# micro.net
KiCad netlist of a schematic drawn in Altium Designer
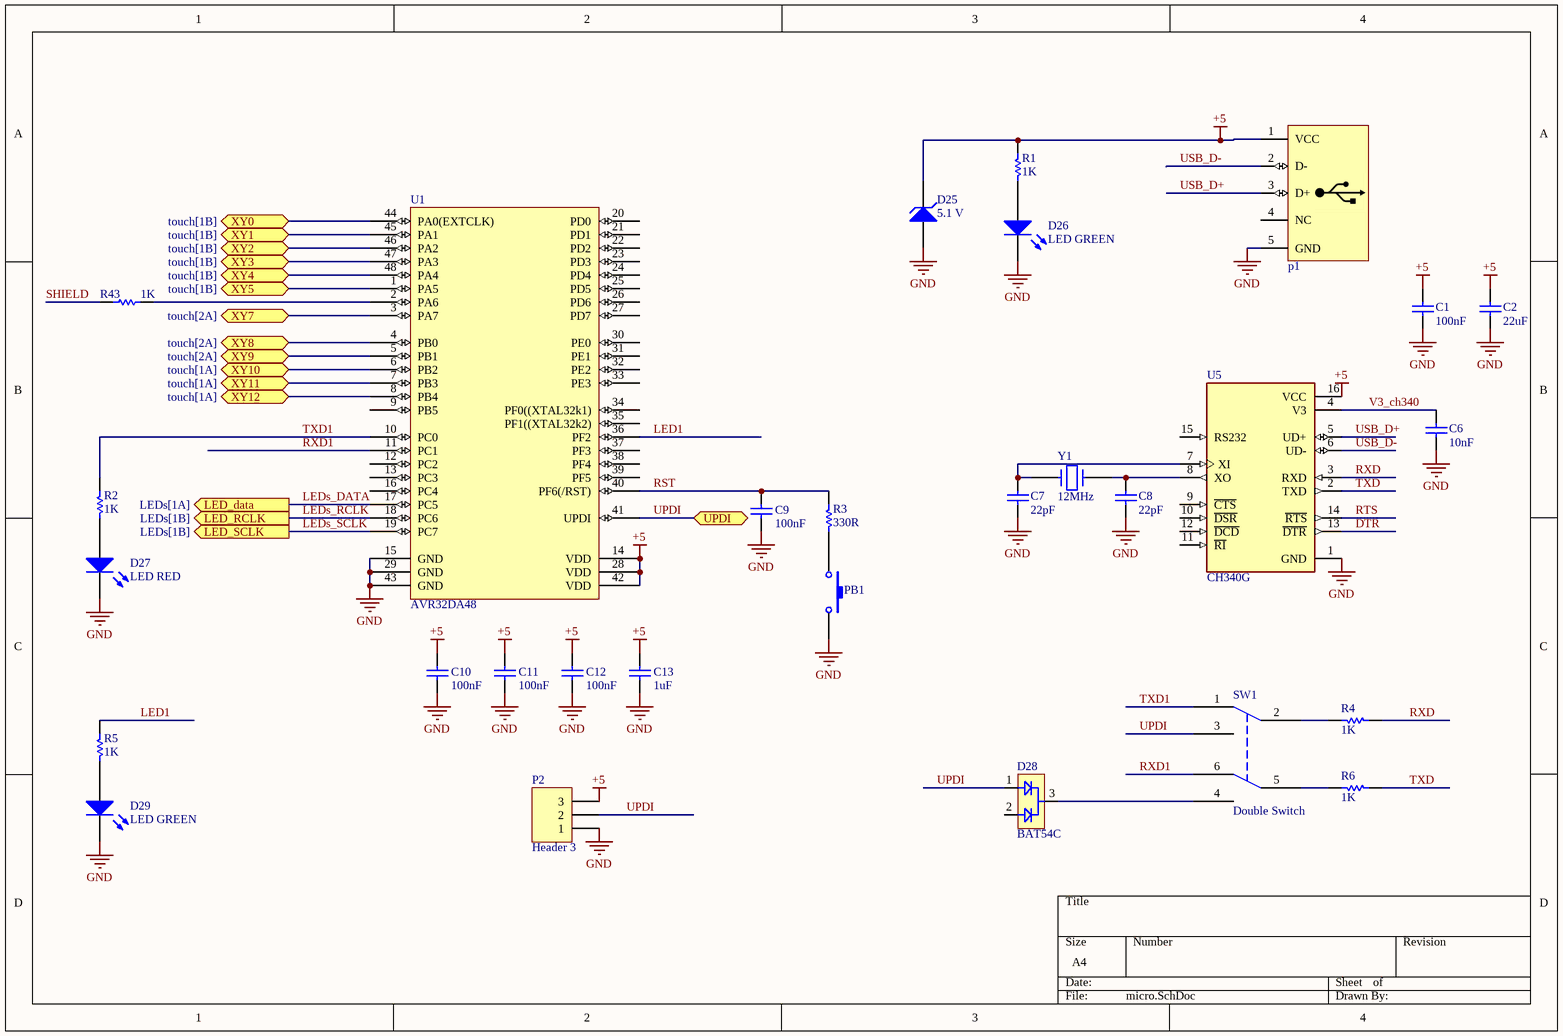
[diagram p0: micro.SchDoc]

(export (version "E")
  (design (tool "Eeschema 10.0.6"))
  (components
    (comp (ref "C1")
      (value "100nF")
      (footprint "SMD_CAP_0805")
      (description "CAP SMD 0805")
      (fields (field (name "PUBLISHER") "Altium Limited"))
      (libsource (lib "Miscellaneous Devices") (part "Cap"))
    )
    (comp (ref "C2")
      (value "22uF")
      (footprint "SMD_CAP_0805")
      (description "CAP SMD 0805")
      (fields (field (name "PUBLISHER") "Altium Limited"))
      (libsource (lib "Miscellaneous Devices") (part "Cap"))
    )
    (comp (ref "C6")
      (value "10nF")
      (footprint "SMD_CAP_0805")
      (description "CAP SMD 0805")
      (fields (field (name "PUBLISHER") "Altium Limited"))
      (libsource (lib "Miscellaneous Devices") (part "Cap"))
    )
    (comp (ref "C7")
      (value "22pF")
      (footprint "SMD_CAP_0805")
      (description "CAP SMD 0805")
      (fields (field (name "PUBLISHER") "Altium Limited"))
      (libsource (lib "Miscellaneous Devices") (part "Cap"))
    )
    (comp (ref "C8")
      (value "22pF")
      (footprint "SMD_CAP_0805")
      (description "CAP SMD 0805")
      (fields (field (name "PUBLISHER") "Altium Limited"))
      (libsource (lib "Miscellaneous Devices") (part "Cap"))
    )
    (comp (ref "C9")
      (value "100nF")
      (footprint "CAP0805")
      (description "CAP seramic")
      (fields (field (name "Comment") "cap 100nF"))
      (libsource (lib "Altium library (www.AVRelec.com)") (part "Cap ceramic"))
    )
    (comp (ref "C10")
      (value "100nF")
      (footprint "CAP0805")
      (description "CAP seramic")
      (fields (field (name "Comment") "cap 100nF"))
      (libsource (lib "Altium library (www.AVRelec.com)") (part "Cap ceramic"))
    )
    (comp (ref "C11")
      (value "100nF")
      (footprint "CAP0805")
      (description "CAP seramic")
      (fields (field (name "Comment") "cap 100nF"))
      (libsource (lib "Altium library (www.AVRelec.com)") (part "Cap ceramic"))
    )
    (comp (ref "C12")
      (value "100nF")
      (footprint "CAP0805")
      (description "CAP seramic")
      (fields (field (name "Comment") "cap 100nF"))
      (libsource (lib "Altium library (www.AVRelec.com)") (part "Cap ceramic"))
    )
    (comp (ref "C13")
      (value "1uF")
      (footprint "CAP0805")
      (description "CAP seramic")
      (fields (field (name "Comment") "cap 1uF"))
      (libsource (lib "Altium library (www.AVRelec.com)") (part "Cap ceramic"))
    )
    (comp (ref "D25")
      (value "Diode Zener")
      (footprint "Diode 1n4148 SMD")
      (description "Zener Diode")
      (fields (field (name "VOLTAGE") "5.1 V") (field (name "DESIGNER") "Saeid Jorablo"))
      (libsource (lib "Altium") (part "Diode Zener"))
    )
    (comp (ref "D26")
      (value "LED GREEN")
      (footprint "LED_0805 G")
      (description "LED SMD 0805 GREEN")
      (fields (field (name "PUBLISHER") "Altium Limited"))
      (libsource (lib "Miscellaneous Devices") (part "LED0"))
    )
    (comp (ref "D27")
      (value "LED RED")
      (footprint "LED_0805 G")
      (description "LED SMD 0805 RED")
      (fields (field (name "PUBLISHER") "Altium Limited"))
      (libsource (lib "Miscellaneous Devices") (part "LED0"))
    )
    (comp (ref "D28") (value "BAT54C") (footprint "SOT-23") (libsource (lib "ZetaBoard_Lib") (part "BAT54C")))
    (comp (ref "D29")
      (value "LED GREEN")
      (footprint "LED_0805 G")
      (description "LED SMD 0805 GREEN")
      (fields (field (name "PUBLISHER") "Altium Limited"))
      (libsource (lib "Miscellaneous Devices") (part "LED0"))
    )
    (comp (ref "p1")
      (value "USB Connector")
      (footprint "USB_AB_BM_SHS")
      (description "USB Connector MICRO-B Type")
      (fields (field (name "DESIGNER") "ABBAS BASEREH") (field (name "PUBLISHER") "ABBAS BASEREH"))
      (libsource (lib "Altium (2)") (part "USB MICRO"))
    )
    (comp (ref "P2")
      (value "Header 3")
      (footprint "HDR1X3")
      (description "Header, 3-Pin")
      (fields (field (name "PUBLISHER") "Altium Limited"))
      (libsource (lib "Miscellaneous Connectors") (part "Header 3"))
    )
    (comp (ref "PB1")
      (value "Push-Button-tall")
      (footprint "tack-sw-3x5x6")
      (libsource (lib "Mine-Discreet") (part "Push-Button-tall"))
    )
    (comp (ref "R1")
      (value "1K")
      (footprint "RES0805")
      (description "Resistor")
      (fields (field (name "Comment") "Res 1K") (field (name "PUBLISHER") "Altium Limited"))
      (libsource (lib "Miscellaneous Devices") (part "Res1"))
    )
    (comp (ref "R2")
      (value "1K")
      (footprint "RES0805")
      (description "Resistor")
      (fields (field (name "Comment") "Res 1K") (field (name "PUBLISHER") "Altium Limited"))
      (libsource (lib "Miscellaneous Devices") (part "Res1"))
    )
    (comp (ref "R3")
      (value "330R")
      (footprint "RES0805")
      (description "Resistor")
      (fields (field (name "Comment") "Res 330R") (field (name "PUBLISHER") "Altium Limited"))
      (libsource (lib "Miscellaneous Devices") (part "Res1"))
    )
    (comp (ref "R4")
      (value "1K")
      (footprint "RES0805")
      (description "Resistor")
      (fields (field (name "Comment") "Res 1K") (field (name "PUBLISHER") "Altium Limited"))
      (libsource (lib "Miscellaneous Devices") (part "Res1"))
    )
    (comp (ref "R5")
      (value "1K")
      (footprint "RES0805")
      (description "Resistor")
      (fields (field (name "Comment") "Res 1K") (field (name "PUBLISHER") "Altium Limited"))
      (libsource (lib "Miscellaneous Devices") (part "Res1"))
    )
    (comp (ref "R6")
      (value "1K")
      (footprint "RES0805")
      (description "Resistor")
      (fields (field (name "Comment") "Res 1K") (field (name "PUBLISHER") "Altium Limited"))
      (libsource (lib "Miscellaneous Devices") (part "Res1"))
    )
    (comp (ref "R43")
      (value "1K")
      (footprint "RES 0805 (2012X06L)")
      (description "Resistor")
      (fields (field (name "PUBLISHER") "Altium Limited"))
      (libsource (lib "Miscellaneous Devices") (part "Res1"))
    )
    (comp (ref "SW1")
      (value "Double Switch")
      (footprint "switch_2way_DPDT_right")
      (description "DPDT Switch")
      (libsource (lib "My Library") (part "Switch - DPDT"))
    )
    (comp (ref "U1")
      (value "AVR32DA48")
      (footprint "TQPF48")
      (libsource (lib "AVR_DA_family") (part "AVR32DA48"))
    )
    (comp (ref "U5")
      (value "CH340G")
      (footprint "SOIC16_N")
      (description "USB Interface Integrated Circuit")
      (fields (field (name "MP") "Ch340G") (field (name "MF") "WCH"))
      (libsource (lib "ESP32") (part "CH340G"))
    )
    (comp (ref "Y1")
      (value "12MHz")
      (footprint "XTAL_SMD")
      (description "Crystal")
      (libsource (lib "Altium library (www.AVRelec.com)") (part "CRYSTAL"))
    )
  )
  (nets
    (net (code "1") (name "+5") (class "Default")
      (node (ref "C1") (pin "2") (pinfunction "2_2") (pintype "passive"))
      (node (ref "C10") (pin "2") (pinfunction "2_2") (pintype "passive"))
      (node (ref "C11") (pin "2") (pinfunction "2_2") (pintype "passive"))
      (node (ref "C12") (pin "2") (pinfunction "2_2") (pintype "passive"))
      (node (ref "C13") (pin "2") (pinfunction "2_2") (pintype "passive"))
      (node (ref "C2") (pin "2") (pinfunction "2_2") (pintype "passive"))
      (node (ref "D25") (pin "2") (pinfunction "K_2") (pintype "passive"))
      (node (ref "P2") (pin "3") (pinfunction "3_3") (pintype "passive"))
      (node (ref "R1") (pin "1") (pinfunction "1_1") (pintype "passive"))
      (node (ref "U1") (pin "14") (pinfunction "VDD_14") (pintype "power_in"))
      (node (ref "U1") (pin "28") (pinfunction "VDD_28") (pintype "power_in"))
      (node (ref "U1") (pin "42") (pinfunction "VDD_42") (pintype "power_in"))
      (node (ref "U5") (pin "16") (pinfunction "VCC_16") (pintype "power_in"))
      (node (ref "p1") (pin "1") (pinfunction "VCC_1") (pintype "power_in"))
    )
    (net (code "2") (name "/DTR") (class "Default")
      (node (ref "U5") (pin "13") (pinfunction "~{DTR}_13") (pintype "output"))
    )
    (net (code "3") (name "/LED1") (class "Default")
      (node (ref "R5") (pin "1") (pinfunction "1_1") (pintype "passive"))
      (node (ref "U1") (pin "36") (pinfunction "PF2_36") (pintype "bidirectional"))
    )
    (net (code "4") (name "/LEDs_DATA") (class "Default")
      (node (ref "U1") (pin "17") (pinfunction "PC5_17") (pintype "bidirectional"))
    )
    (net (code "5") (name "/LEDs_RCLK") (class "Default")
      (node (ref "U1") (pin "18") (pinfunction "PC6_18") (pintype "bidirectional"))
    )
    (net (code "6") (name "/LEDs_SCLK") (class "Default")
      (node (ref "U1") (pin "19") (pinfunction "PC7_19") (pintype "bidirectional"))
    )
    (net (code "7") (name "/RST") (class "Default")
      (node (ref "C9") (pin "2") (pinfunction "2_2") (pintype "passive"))
      (node (ref "R3") (pin "1") (pinfunction "1_1") (pintype "passive"))
      (node (ref "U1") (pin "40") (pinfunction "PF6(/RST)_40") (pintype "bidirectional"))
    )
    (net (code "8") (name "/RTS") (class "Default")
      (node (ref "U5") (pin "14") (pinfunction "~{RTS}_14") (pintype "output"))
    )
    (net (code "9") (name "/RXD") (class "Default")
      (node (ref "R4") (pin "2") (pinfunction "2_2") (pintype "passive"))
      (node (ref "U5") (pin "3") (pinfunction "RXD_3") (pintype "input"))
    )
    (net (code "10") (name "/RXD1") (class "Default")
      (node (ref "SW1") (pin "6") (pinfunction "6_6") (pintype "passive"))
      (node (ref "U1") (pin "11") (pinfunction "PC1_11") (pintype "bidirectional"))
    )
    (net (code "11") (name "/SHIELD") (class "Default")
      (node (ref "R43") (pin "2") (pinfunction "2_2") (pintype "passive"))
    )
    (net (code "12") (name "/TXD") (class "Default")
      (node (ref "R6") (pin "2") (pinfunction "2_2") (pintype "passive"))
      (node (ref "U5") (pin "2") (pinfunction "TXD_2") (pintype "output"))
    )
    (net (code "13") (name "/TXD1") (class "Default")
      (node (ref "R2") (pin "1") (pinfunction "1_1") (pintype "passive"))
      (node (ref "SW1") (pin "1") (pinfunction "1_1") (pintype "passive"))
      (node (ref "U1") (pin "10") (pinfunction "PC0_10") (pintype "bidirectional"))
    )
    (net (code "14") (name "/UPDI") (class "Default")
      (node (ref "D28") (pin "1") (pintype "passive"))
      (node (ref "P2") (pin "2") (pinfunction "2_2") (pintype "passive"))
      (node (ref "SW1") (pin "3") (pinfunction "3_3") (pintype "passive"))
      (node (ref "U1") (pin "41") (pinfunction "UPDI_41") (pintype "bidirectional"))
    )
    (net (code "15") (name "/USB_D+") (class "Default")
      (node (ref "U5") (pin "5") (pinfunction "UD+_5") (pintype "bidirectional"))
      (node (ref "p1") (pin "3") (pinfunction "D+_3") (pintype "bidirectional"))
    )
    (net (code "16") (name "/USB_D-") (class "Default")
      (node (ref "U5") (pin "6") (pinfunction "UD-_6") (pintype "bidirectional"))
      (node (ref "p1") (pin "2") (pinfunction "D-_2") (pintype "bidirectional"))
    )
    (net (code "17") (name "/V3_ch340") (class "Default")
      (node (ref "C6") (pin "2") (pinfunction "2_2") (pintype "passive"))
      (node (ref "U5") (pin "4") (pinfunction "V3_4") (pintype "power_in"))
    )
    (net (code "18") (name "/XY0") (class "Default")
      (node (ref "U1") (pin "44") (pinfunction "PA0(EXTCLK)_44") (pintype "bidirectional"))
    )
    (net (code "19") (name "/XY1") (class "Default")
      (node (ref "U1") (pin "45") (pinfunction "PA1_45") (pintype "bidirectional"))
    )
    (net (code "20") (name "/XY2") (class "Default")
      (node (ref "U1") (pin "46") (pinfunction "PA2_46") (pintype "bidirectional"))
    )
    (net (code "21") (name "/XY3") (class "Default")
      (node (ref "U1") (pin "47") (pinfunction "PA3_47") (pintype "bidirectional"))
    )
    (net (code "22") (name "/XY4") (class "Default")
      (node (ref "U1") (pin "48") (pinfunction "PA4_48") (pintype "bidirectional"))
    )
    (net (code "23") (name "/XY5") (class "Default")
      (node (ref "U1") (pin "1") (pinfunction "PA5_1") (pintype "bidirectional"))
    )
    (net (code "24") (name "/XY7") (class "Default")
      (node (ref "U1") (pin "3") (pinfunction "PA7_3") (pintype "bidirectional"))
    )
    (net (code "25") (name "/XY8") (class "Default")
      (node (ref "U1") (pin "4") (pinfunction "PB0_4") (pintype "bidirectional"))
    )
    (net (code "26") (name "/XY9") (class "Default")
      (node (ref "U1") (pin "5") (pinfunction "PB1_5") (pintype "bidirectional"))
    )
    (net (code "27") (name "/XY10") (class "Default")
      (node (ref "U1") (pin "6") (pinfunction "PB2_6") (pintype "bidirectional"))
    )
    (net (code "28") (name "/XY11") (class "Default")
      (node (ref "U1") (pin "7") (pinfunction "PB3_7") (pintype "bidirectional"))
    )
    (net (code "29") (name "/XY12") (class "Default")
      (node (ref "U1") (pin "8") (pinfunction "PB4_8") (pintype "bidirectional"))
    )
    (net (code "30") (name "GND") (class "Default")
      (node (ref "C1") (pin "1") (pinfunction "1_1") (pintype "passive"))
      (node (ref "C10") (pin "1") (pinfunction "1_1") (pintype "passive"))
      (node (ref "C11") (pin "1") (pinfunction "1_1") (pintype "passive"))
      (node (ref "C12") (pin "1") (pinfunction "1_1") (pintype "passive"))
      (node (ref "C13") (pin "1") (pinfunction "1_1") (pintype "passive"))
      (node (ref "C2") (pin "1") (pinfunction "1_1") (pintype "passive"))
      (node (ref "C6") (pin "1") (pinfunction "1_1") (pintype "passive"))
      (node (ref "C7") (pin "1") (pinfunction "1_1") (pintype "passive"))
      (node (ref "C8") (pin "1") (pinfunction "1_1") (pintype "passive"))
      (node (ref "C9") (pin "1") (pinfunction "1_1") (pintype "passive"))
      (node (ref "D25") (pin "1") (pinfunction "A_1") (pintype "passive"))
      (node (ref "D26") (pin "2") (pinfunction "K_2") (pintype "passive"))
      (node (ref "D27") (pin "2") (pinfunction "K_2") (pintype "passive"))
      (node (ref "D29") (pin "2") (pinfunction "K_2") (pintype "passive"))
      (node (ref "P2") (pin "1") (pinfunction "1_1") (pintype "passive"))
      (node (ref "PB1") (pin "1") (pinfunction "1_1") (pintype "passive"))
      (node (ref "U1") (pin "15") (pinfunction "GND_15") (pintype "power_in"))
      (node (ref "U1") (pin "29") (pinfunction "GND_29") (pintype "power_in"))
      (node (ref "U1") (pin "43") (pinfunction "GND_43") (pintype "power_in"))
      (node (ref "U5") (pin "1") (pinfunction "GND_1") (pintype "power_in"))
      (node (ref "p1") (pin "5") (pinfunction "GND_5") (pintype "power_in"))
    )
    (net (code "31") (name "Net-(D26-A)") (class "Default")
      (node (ref "D26") (pin "1") (pinfunction "A_1") (pintype "passive"))
      (node (ref "R1") (pin "2") (pinfunction "2_2") (pintype "passive"))
    )
    (net (code "32") (name "Net-(D27-A)") (class "Default")
      (node (ref "D27") (pin "1") (pinfunction "A_1") (pintype "passive"))
      (node (ref "R2") (pin "2") (pinfunction "2_2") (pintype "passive"))
    )
    (net (code "33") (name "Net-(D28-Pad3)") (class "Default")
      (node (ref "D28") (pin "3") (pintype "passive"))
      (node (ref "SW1") (pin "4") (pinfunction "4_4") (pintype "passive"))
    )
    (net (code "34") (name "Net-(D29-A)") (class "Default")
      (node (ref "D29") (pin "1") (pinfunction "A_1") (pintype "passive"))
      (node (ref "R5") (pin "2") (pinfunction "2_2") (pintype "passive"))
    )
    (net (code "35") (name "Net-(PB1-Pad2)") (class "Default")
      (node (ref "PB1") (pin "2") (pinfunction "2_2") (pintype "passive"))
      (node (ref "R3") (pin "2") (pinfunction "2_2") (pintype "passive"))
    )
    (net (code "36") (name "Net-(R4-Pad1)") (class "Default")
      (node (ref "R4") (pin "1") (pinfunction "1_1") (pintype "passive"))
      (node (ref "SW1") (pin "2") (pinfunction "2_2") (pintype "passive"))
    )
    (net (code "37") (name "Net-(R6-Pad1)") (class "Default")
      (node (ref "R6") (pin "1") (pinfunction "1_1") (pintype "passive"))
      (node (ref "SW1") (pin "5") (pinfunction "5_5") (pintype "passive"))
    )
    (net (code "38") (name "Net-(U1-PA6)") (class "Default")
      (node (ref "R43") (pin "1") (pinfunction "1_1") (pintype "passive"))
      (node (ref "U1") (pin "2") (pinfunction "PA6_2") (pintype "bidirectional"))
    )
    (net (code "39") (name "Net-(U5-XI)") (class "Default")
      (node (ref "C7") (pin "2") (pinfunction "2_2") (pintype "passive"))
      (node (ref "U5") (pin "7") (pinfunction "XI_7") (pintype "input"))
      (node (ref "Y1") (pin "1") (pinfunction "1_1") (pintype "passive"))
    )
    (net (code "40") (name "Net-(U5-XO)") (class "Default")
      (node (ref "C8") (pin "2") (pinfunction "2_2") (pintype "passive"))
      (node (ref "U5") (pin "8") (pinfunction "XO_8") (pintype "output"))
      (node (ref "Y1") (pin "2") (pinfunction "2_2") (pintype "passive"))
    )
    (net (code "41") (name "unconnected-(D28-Pad2)") (class "Default")
      (node (ref "D28") (pin "2") (pintype "passive"))
    )
    (net (code "42") (name "unconnected-(U1-PB5-Pad9)") (class "Default")
      (node (ref "U1") (pin "9") (pinfunction "PB5_9") (pintype "bidirectional"))
    )
    (net (code "43") (name "unconnected-(U1-PC2-Pad12)") (class "Default")
      (node (ref "U1") (pin "12") (pinfunction "PC2_12") (pintype "bidirectional"))
    )
    (net (code "44") (name "unconnected-(U1-PC3-Pad13)") (class "Default")
      (node (ref "U1") (pin "13") (pinfunction "PC3_13") (pintype "bidirectional"))
    )
    (net (code "45") (name "unconnected-(U1-PC4-Pad16)") (class "Default")
      (node (ref "U1") (pin "16") (pinfunction "PC4_16") (pintype "bidirectional"))
    )
    (net (code "46") (name "unconnected-(U1-PD0-Pad20)") (class "Default")
      (node (ref "U1") (pin "20") (pinfunction "PD0_20") (pintype "bidirectional"))
    )
    (net (code "47") (name "unconnected-(U1-PD1-Pad21)") (class "Default")
      (node (ref "U1") (pin "21") (pinfunction "PD1_21") (pintype "bidirectional"))
    )
    (net (code "48") (name "unconnected-(U1-PD2-Pad22)") (class "Default")
      (node (ref "U1") (pin "22") (pinfunction "PD2_22") (pintype "bidirectional"))
    )
    (net (code "49") (name "unconnected-(U1-PD3-Pad23)") (class "Default")
      (node (ref "U1") (pin "23") (pinfunction "PD3_23") (pintype "bidirectional"))
    )
    (net (code "50") (name "unconnected-(U1-PD4-Pad24)") (class "Default")
      (node (ref "U1") (pin "24") (pinfunction "PD4_24") (pintype "bidirectional"))
    )
    (net (code "51") (name "unconnected-(U1-PD5-Pad25)") (class "Default")
      (node (ref "U1") (pin "25") (pinfunction "PD5_25") (pintype "bidirectional"))
    )
    (net (code "52") (name "unconnected-(U1-PD6-Pad26)") (class "Default")
      (node (ref "U1") (pin "26") (pinfunction "PD6_26") (pintype "bidirectional"))
    )
    (net (code "53") (name "unconnected-(U1-PD7-Pad27)") (class "Default")
      (node (ref "U1") (pin "27") (pinfunction "PD7_27") (pintype "bidirectional"))
    )
    (net (code "54") (name "unconnected-(U1-PE0-Pad30)") (class "Default")
      (node (ref "U1") (pin "30") (pinfunction "PE0_30") (pintype "bidirectional"))
    )
    (net (code "55") (name "unconnected-(U1-PE1-Pad31)") (class "Default")
      (node (ref "U1") (pin "31") (pinfunction "PE1_31") (pintype "bidirectional"))
    )
    (net (code "56") (name "unconnected-(U1-PE2-Pad32)") (class "Default")
      (node (ref "U1") (pin "32") (pinfunction "PE2_32") (pintype "bidirectional"))
    )
    (net (code "57") (name "unconnected-(U1-PE3-Pad33)") (class "Default")
      (node (ref "U1") (pin "33") (pinfunction "PE3_33") (pintype "bidirectional"))
    )
    (net (code "58") (name "unconnected-(U1-PF0((XTAL32k1)-Pad34)") (class "Default")
      (node (ref "U1") (pin "34") (pinfunction "PF0((XTAL32k1)_34") (pintype "bidirectional"))
    )
    (net (code "59") (name "unconnected-(U1-PF1((XTAL32k2)-Pad35)") (class "Default")
      (node (ref "U1") (pin "35") (pinfunction "PF1((XTAL32k2)_35") (pintype "bidirectional"))
    )
    (net (code "60") (name "unconnected-(U1-PF3-Pad37)") (class "Default")
      (node (ref "U1") (pin "37") (pinfunction "PF3_37") (pintype "bidirectional"))
    )
    (net (code "61") (name "unconnected-(U1-PF4-Pad38)") (class "Default")
      (node (ref "U1") (pin "38") (pinfunction "PF4_38") (pintype "bidirectional"))
    )
    (net (code "62") (name "unconnected-(U1-PF5-Pad39)") (class "Default")
      (node (ref "U1") (pin "39") (pinfunction "PF5_39") (pintype "bidirectional"))
    )
    (net (code "63") (name "unconnected-(U5-RS232-Pad15)") (class "Default")
      (node (ref "U5") (pin "15") (pinfunction "RS232_15") (pintype "input"))
    )
    (net (code "64") (name "unconnected-(U5-~{CTS}-Pad9)") (class "Default")
      (node (ref "U5") (pin "9") (pinfunction "~{CTS}_9") (pintype "input"))
    )
    (net (code "65") (name "unconnected-(U5-~{DCD}-Pad12)") (class "Default")
      (node (ref "U5") (pin "12") (pinfunction "~{DCD}_12") (pintype "input"))
    )
    (net (code "66") (name "unconnected-(U5-~{DSR}-Pad10)") (class "Default")
      (node (ref "U5") (pin "10") (pinfunction "~{DSR}_10") (pintype "input"))
    )
    (net (code "67") (name "unconnected-(U5-~{RI}-Pad11)") (class "Default")
      (node (ref "U5") (pin "11") (pinfunction "~{RI}_11") (pintype "input"))
    )
    (net (code "68") (name "unconnected-(p1-NC-Pad4)") (class "Default")
      (node (ref "p1") (pin "4") (pinfunction "NC_4") (pintype "passive"))
    )
  )
)
